# MainSchematic.net
KiCad netlist of a schematic drawn in Altium Designer
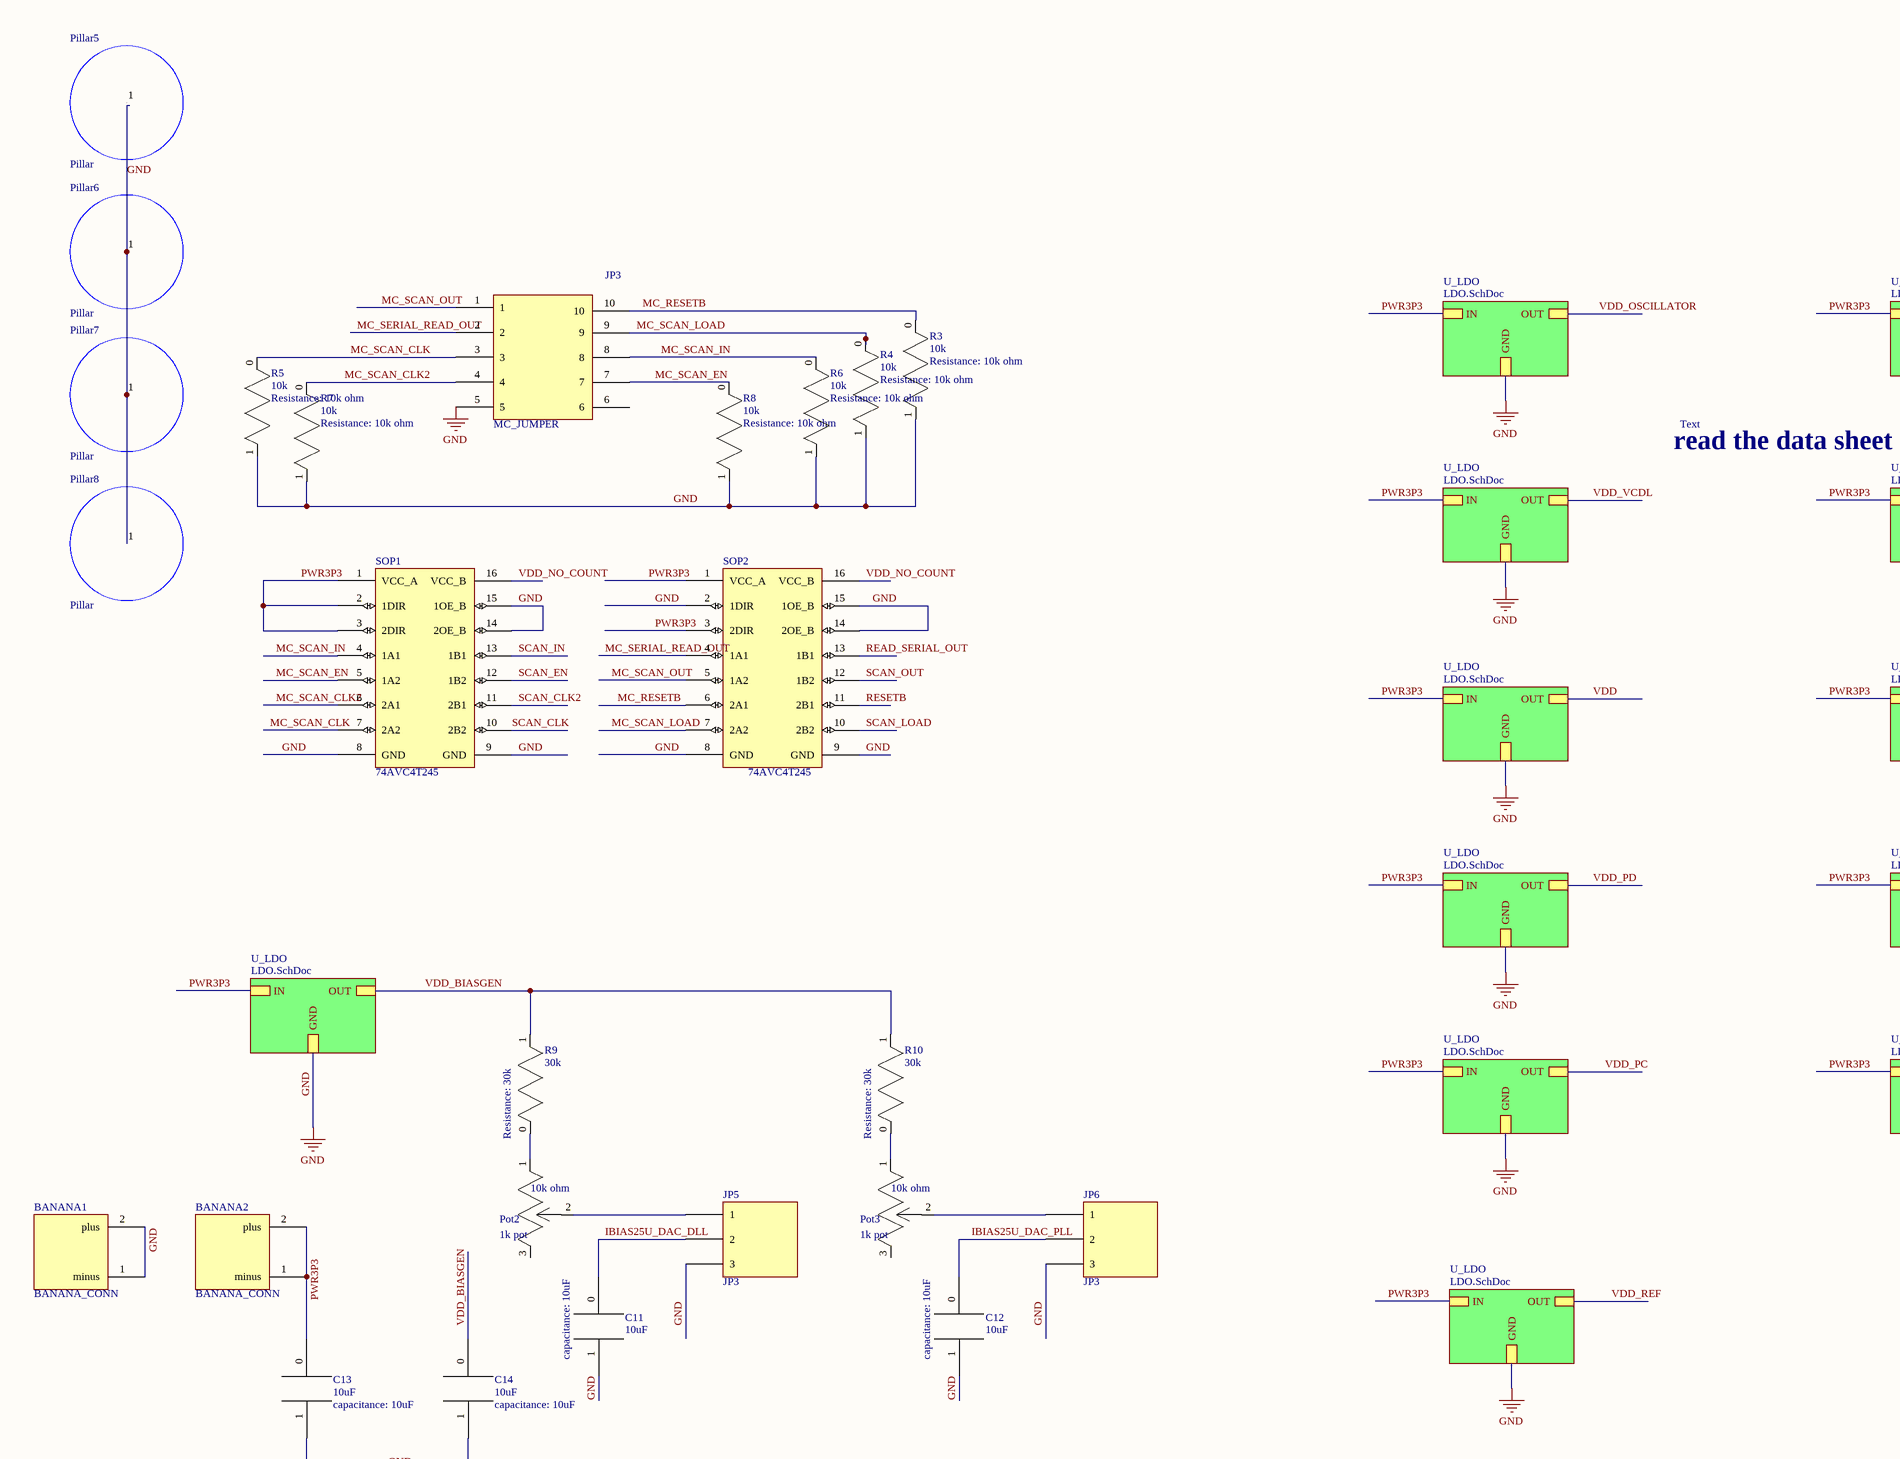
[diagram p0: MainSchematic.SchDoc, top left]
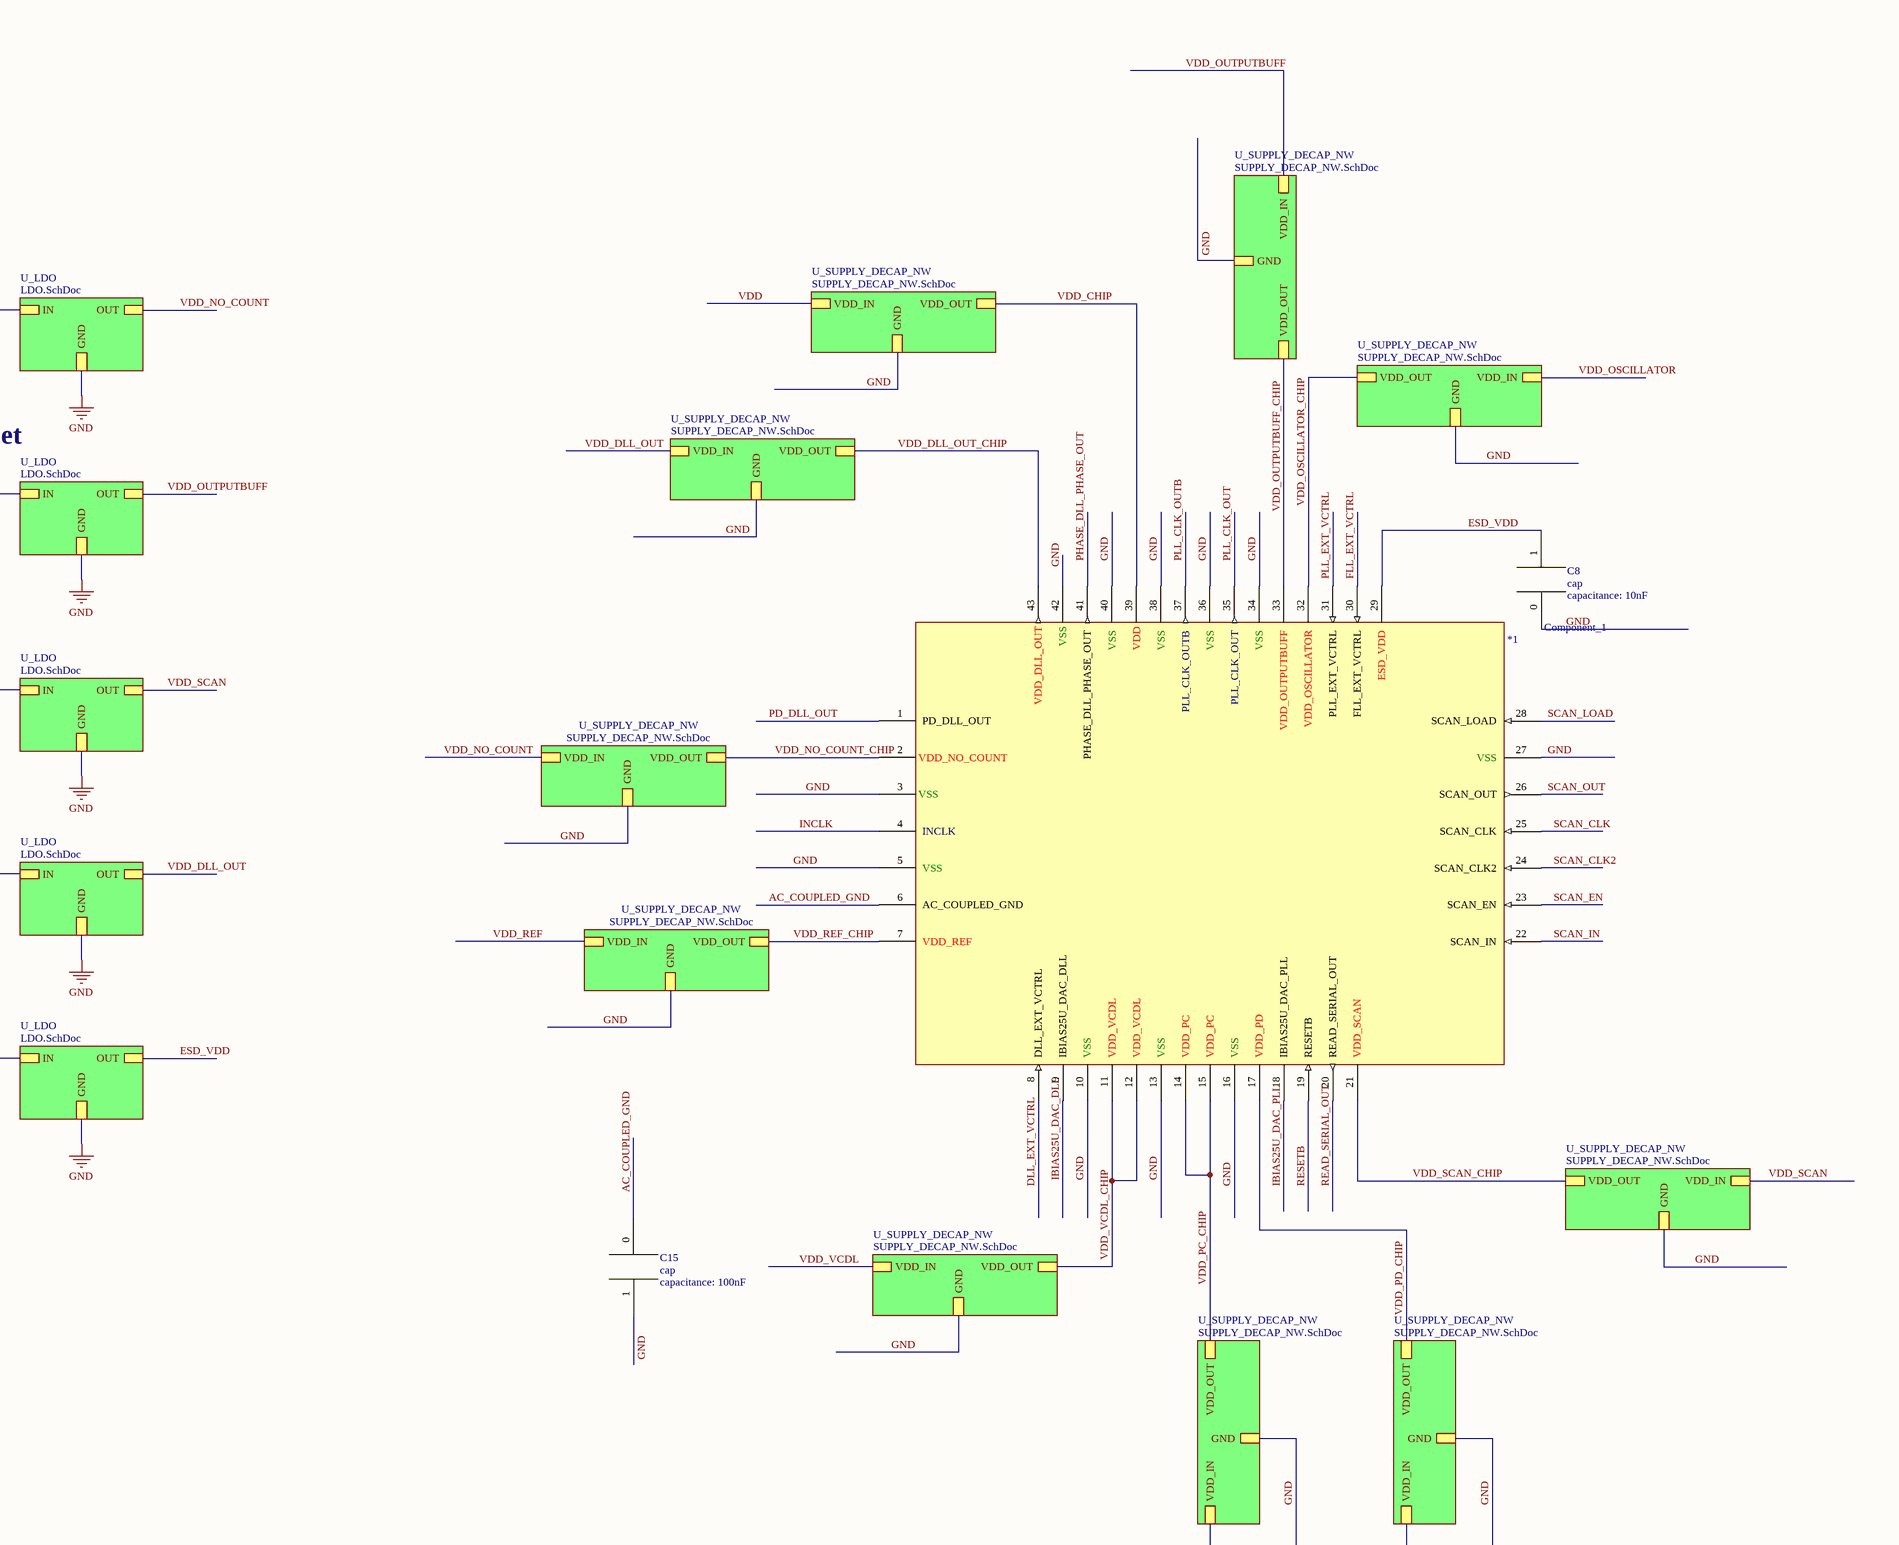
[diagram p1: MainSchematic.SchDoc, top right]
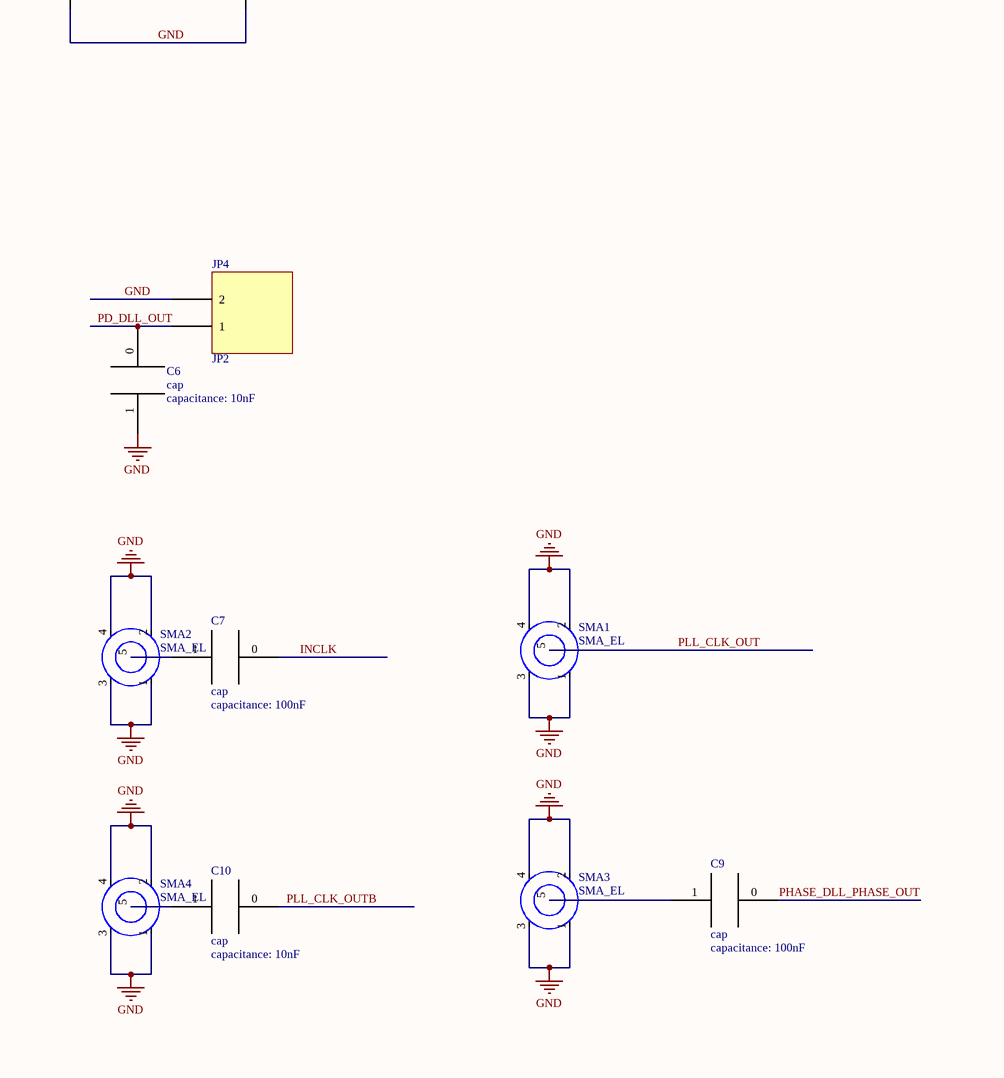
[diagram p2: MainSchematic.SchDoc, bottom left]
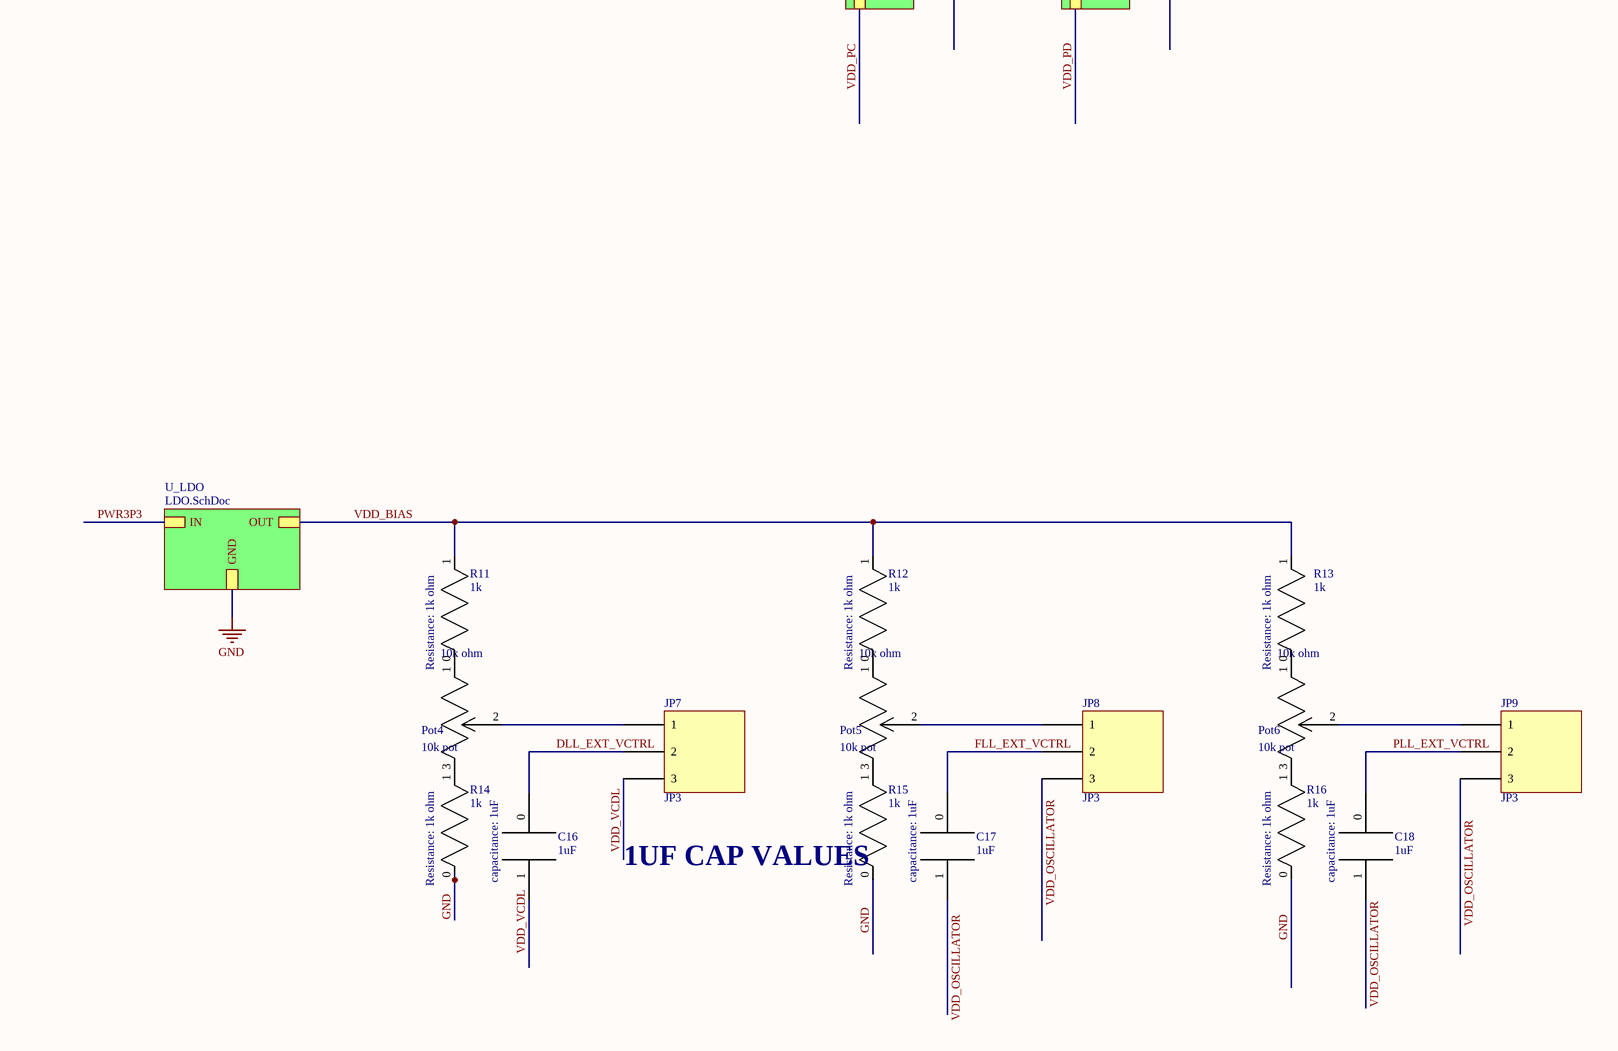
[diagram p3: MainSchematic.SchDoc, bottom right]

(export (version "E")
  (design (tool "Eeschema 10.0.6"))
  (components
    (comp (ref "*1")
      (value "Component_1")
      (footprint "PCBComponent_1")
      (libsource (lib "PLL_CHIP") (part "Component_1"))
    )
    (comp (ref "BANANA1")
      (value "BANANA_CONN")
      (footprint "BANANA_CONN")
      (libsource (lib "Integrated_Library_Da2016") (part "BANANA_CONN"))
    )
    (comp (ref "BANANA2")
      (value "BANANA_CONN")
      (footprint "BANANA_CONN")
      (libsource (lib "Integrated_Library_Da2016") (part "BANANA_CONN"))
    )
    (comp (ref "C6")
      (value "cap")
      (footprint "Capacitor")
      (description "0603cap")
      (fields (field (name "CAPACITANCE") "10nF"))
      (libsource (lib "Integrated_Library_Da2016") (part "cap"))
    )
    (comp (ref "C7")
      (value "cap")
      (footprint "Capacitor")
      (description "0603cap")
      (fields (field (name "CAPACITANCE") "100nF"))
      (libsource (lib "Integrated_Library_Da2016") (part "cap"))
    )
    (comp (ref "C8")
      (value "cap")
      (footprint "Capacitor")
      (description "0603cap")
      (fields (field (name "CAPACITANCE") "10nF"))
      (libsource (lib "Integrated_Library_Da2016") (part "cap"))
    )
    (comp (ref "C9")
      (value "cap")
      (footprint "Capacitor")
      (description "0603cap")
      (fields (field (name "CAPACITANCE") "100nF"))
      (libsource (lib "Integrated_Library_Da2016") (part "cap"))
    )
    (comp (ref "C10")
      (value "cap")
      (footprint "Capacitor")
      (description "0603cap")
      (fields (field (name "CAPACITANCE") "10nF"))
      (libsource (lib "Integrated_Library_Da2016") (part "cap"))
    )
    (comp (ref "C11")
      (value "10uF")
      (footprint "Capacitor")
      (description "0603cap")
      (fields (field (name "CAPACITANCE") "10uF"))
      (libsource (lib "Integrated_Library_Da2016") (part "cap"))
    )
    (comp (ref "C12")
      (value "10uF")
      (footprint "Capacitor")
      (description "0603cap")
      (fields (field (name "CAPACITANCE") "10uF"))
      (libsource (lib "Integrated_Library_Da2016") (part "cap"))
    )
    (comp (ref "C13")
      (value "10uF")
      (footprint "Capacitor")
      (description "0603cap")
      (fields (field (name "CAPACITANCE") "10uF"))
      (libsource (lib "Integrated_Library_Da2016") (part "cap"))
    )
    (comp (ref "C14")
      (value "10uF")
      (footprint "Capacitor")
      (description "0603cap")
      (fields (field (name "CAPACITANCE") "10uF"))
      (libsource (lib "Integrated_Library_Da2016") (part "cap"))
    )
    (comp (ref "C15")
      (value "cap")
      (footprint "Capacitor")
      (description "0603cap")
      (fields (field (name "CAPACITANCE") "100nF"))
      (libsource (lib "Integrated_Library_Da2016") (part "cap"))
    )
    (comp (ref "C16")
      (value "1uF")
      (footprint "Capacitor")
      (description "0603cap")
      (fields (field (name "CAPACITANCE") "1uF"))
      (libsource (lib "Integrated_Library_Da2016") (part "cap"))
    )
    (comp (ref "C17")
      (value "1uF")
      (footprint "Capacitor")
      (description "0603cap")
      (fields (field (name "CAPACITANCE") "1uF"))
      (libsource (lib "Integrated_Library_Da2016") (part "cap"))
    )
    (comp (ref "C18")
      (value "1uF")
      (footprint "Capacitor")
      (description "0603cap")
      (fields (field (name "CAPACITANCE") "1uF"))
      (libsource (lib "Integrated_Library_Da2016") (part "cap"))
    )
    (comp (ref "JP3")
      (value "MC_JUMPER")
      (footprint "JUMPER10")
      (description "Jumper_10p")
      (libsource (lib "Integrated_Library_Da2016") (part "Jumper_10"))
    )
    (comp (ref "JP4")
      (value "JP2")
      (footprint "JUMPER2")
      (description "Jumper_2")
      (libsource (lib "Integrated_Library_Da2016") (part "Jumper_2"))
    )
    (comp (ref "JP5")
      (value "JP3")
      (footprint "JUMPER3")
      (description "Jumper_3p")
      (libsource (lib "Integrated_Library_Da2016") (part "Jumper_3"))
    )
    (comp (ref "JP6")
      (value "JP3")
      (footprint "JUMPER3")
      (description "Jumper_3p")
      (libsource (lib "Integrated_Library_Da2016") (part "Jumper_3"))
    )
    (comp (ref "JP7")
      (value "JP3")
      (footprint "JUMPER3")
      (description "Jumper_3p")
      (libsource (lib "Integrated_Library_Da2016") (part "Jumper_3"))
    )
    (comp (ref "JP8")
      (value "JP3")
      (footprint "JUMPER3")
      (description "Jumper_3p")
      (libsource (lib "Integrated_Library_Da2016") (part "Jumper_3"))
    )
    (comp (ref "JP9")
      (value "JP3")
      (footprint "JUMPER3")
      (description "Jumper_3p")
      (libsource (lib "Integrated_Library_Da2016") (part "Jumper_3"))
    )
    (comp (ref "Pillar5")
      (value "Pillar")
      (footprint "Pillar_hole")
      (libsource (lib "Integrated_Library_Da2016") (part "Pillar_hole"))
    )
    (comp (ref "Pillar6")
      (value "Pillar")
      (footprint "Pillar_hole")
      (libsource (lib "Integrated_Library_Da2016") (part "Pillar_hole"))
    )
    (comp (ref "Pillar7")
      (value "Pillar")
      (footprint "Pillar_hole")
      (libsource (lib "Integrated_Library_Da2016") (part "Pillar_hole"))
    )
    (comp (ref "Pillar8")
      (value "Pillar")
      (footprint "Pillar_hole")
      (libsource (lib "Integrated_Library_Da2016") (part "Pillar_hole"))
    )
    (comp (ref "Pot2")
      (value "1k pot")
      (footprint "Pot")
      (description "Variable Resistor")
      (fields (field (name "RESISTANCE") "10k ohm"))
      (libsource (lib "Integrated_Library_Da2016") (part "Pot"))
    )
    (comp (ref "Pot3")
      (value "1k pot")
      (footprint "Pot")
      (description "Variable Resistor")
      (fields (field (name "RESISTANCE") "10k ohm"))
      (libsource (lib "Integrated_Library_Da2016") (part "Pot"))
    )
    (comp (ref "Pot4")
      (value "10k pot")
      (footprint "Pot")
      (description "Variable Resistor")
      (fields (field (name "RESISTANCE") "10k ohm"))
      (libsource (lib "Integrated_Library_Da2016") (part "Pot"))
    )
    (comp (ref "Pot5")
      (value "10k pot")
      (footprint "Pot")
      (description "Variable Resistor")
      (fields (field (name "RESISTANCE") "10k ohm"))
      (libsource (lib "Integrated_Library_Da2016") (part "Pot"))
    )
    (comp (ref "Pot6")
      (value "10k pot")
      (footprint "Pot")
      (description "Variable Resistor")
      (fields (field (name "RESISTANCE") "10k ohm"))
      (libsource (lib "Integrated_Library_Da2016") (part "Pot"))
    )
    (comp (ref "R3")
      (value "10k")
      (footprint "Resistor")
      (description "0603Res")
      (fields (field (name "RESISTANCE") "10k ohm"))
      (libsource (lib "Integrated_Library_Da2016") (part "res"))
    )
    (comp (ref "R4")
      (value "10k")
      (footprint "Resistor")
      (description "0603Res")
      (fields (field (name "RESISTANCE") "10k ohm"))
      (libsource (lib "Integrated_Library_Da2016") (part "res"))
    )
    (comp (ref "R5")
      (value "10k")
      (footprint "Resistor")
      (description "0603Res")
      (fields (field (name "RESISTANCE") "10k ohm"))
      (libsource (lib "Integrated_Library_Da2016") (part "res"))
    )
    (comp (ref "R6")
      (value "10k")
      (footprint "Resistor")
      (description "0603Res")
      (fields (field (name "RESISTANCE") "10k ohm"))
      (libsource (lib "Integrated_Library_Da2016") (part "res"))
    )
    (comp (ref "R7")
      (value "10k")
      (footprint "Resistor")
      (description "0603Res")
      (fields (field (name "RESISTANCE") "10k ohm"))
      (libsource (lib "Integrated_Library_Da2016") (part "res"))
    )
    (comp (ref "R8")
      (value "10k")
      (footprint "Resistor")
      (description "0603Res")
      (fields (field (name "RESISTANCE") "10k ohm"))
      (libsource (lib "Integrated_Library_Da2016") (part "res"))
    )
    (comp (ref "R9")
      (value "30k")
      (footprint "Resistor")
      (description "0603Res")
      (fields (field (name "RESISTANCE") "30k"))
      (libsource (lib "Integrated_Library_Da2016") (part "res"))
    )
    (comp (ref "R10")
      (value "30k")
      (footprint "Resistor")
      (description "0603Res")
      (fields (field (name "RESISTANCE") "30k"))
      (libsource (lib "Integrated_Library_Da2016") (part "res"))
    )
    (comp (ref "R11")
      (value "1k")
      (footprint "Resistor")
      (description "0603Res")
      (fields (field (name "RESISTANCE") "1k ohm"))
      (libsource (lib "Integrated_Library_Da2016") (part "res"))
    )
    (comp (ref "R12")
      (value "1k")
      (footprint "Resistor")
      (description "0603Res")
      (fields (field (name "RESISTANCE") "1k ohm"))
      (libsource (lib "Integrated_Library_Da2016") (part "res"))
    )
    (comp (ref "R13")
      (value "1k")
      (footprint "Resistor")
      (description "0603Res")
      (fields (field (name "RESISTANCE") "1k ohm"))
      (libsource (lib "Integrated_Library_Da2016") (part "res"))
    )
    (comp (ref "R14")
      (value "1k")
      (footprint "Resistor")
      (description "0603Res")
      (fields (field (name "RESISTANCE") "1k ohm"))
      (libsource (lib "Integrated_Library_Da2016") (part "res"))
    )
    (comp (ref "R15")
      (value "1k")
      (footprint "Resistor")
      (description "0603Res")
      (fields (field (name "RESISTANCE") "1k ohm"))
      (libsource (lib "Integrated_Library_Da2016") (part "res"))
    )
    (comp (ref "R16")
      (value "1k")
      (footprint "Resistor")
      (description "0603Res")
      (fields (field (name "RESISTANCE") "1k ohm"))
      (libsource (lib "Integrated_Library_Da2016") (part "res"))
    )
    (comp (ref "SMA1")
      (value "SMA_EL")
      (footprint "SMA_EL")
      (libsource (lib "Integrated_Library_Da2016") (part "SMA_EL"))
    )
    (comp (ref "SMA2")
      (value "SMA_EL")
      (footprint "SMA_EL")
      (libsource (lib "Integrated_Library_Da2016") (part "SMA_EL"))
    )
    (comp (ref "SMA3")
      (value "SMA_EL")
      (footprint "SMA_EL")
      (libsource (lib "Integrated_Library_Da2016") (part "SMA_EL"))
    )
    (comp (ref "SMA4")
      (value "SMA_EL")
      (footprint "SMA_EL")
      (libsource (lib "Integrated_Library_Da2016") (part "SMA_EL"))
    )
    (comp (ref "SOP1")
      (value "74AVC4T245")
      (footprint "74AVC4T245")
      (description "74AVC4T245 Voltage Shifter")
      (libsource (lib "Integrated_Library_Da2016") (part "74AVC4T245"))
    )
    (comp (ref "SOP2")
      (value "74AVC4T245")
      (footprint "74AVC4T245")
      (description "74AVC4T245 Voltage Shifter")
      (libsource (lib "Integrated_Library_Da2016") (part "74AVC4T245"))
    )
  )
  (nets
    (net (code "1") (name "/AC_COUPLED_GND") (class "Default")
      (node (ref "*1") (pin "6") (pinfunction "AC_COUPLED_GND_6") (pintype "power_in"))
      (node (ref "C15") (pin "0") (pinfunction "0_0") (pintype "passive"))
    )
    (net (code "2") (name "/DLL_EXT_VCTRL") (class "Default")
      (node (ref "*1") (pin "8") (pinfunction "DLL_EXT_VCTRL_8") (pintype "input"))
      (node (ref "C16") (pin "0") (pinfunction "0_0") (pintype "passive"))
      (node (ref "JP7") (pin "2") (pinfunction "2_2") (pintype "passive"))
    )
    (net (code "3") (name "/ESD_VDD") (class "Default")
      (node (ref "*1") (pin "29") (pinfunction "ESD_VDD_29") (pintype "power_in"))
      (node (ref "C8") (pin "1") (pinfunction "1_1") (pintype "passive"))
    )
    (net (code "4") (name "/FLL_EXT_VCTRL") (class "Default")
      (node (ref "*1") (pin "30") (pinfunction "FLL_EXT_VCTRL_30") (pintype "input"))
      (node (ref "C17") (pin "0") (pinfunction "0_0") (pintype "passive"))
      (node (ref "JP8") (pin "2") (pinfunction "2_2") (pintype "passive"))
    )
    (net (code "5") (name "/IBIAS25U_DAC_DLL") (class "Default")
      (node (ref "*1") (pin "9") (pinfunction "IBIAS25U_DAC_DLL_9") (pintype "passive"))
      (node (ref "C11") (pin "0") (pinfunction "0_0") (pintype "passive"))
      (node (ref "JP5") (pin "2") (pinfunction "2_2") (pintype "passive"))
    )
    (net (code "6") (name "/IBIAS25U_DAC_PLL") (class "Default")
      (node (ref "*1") (pin "18") (pinfunction "IBIAS25U_DAC_PLL_18") (pintype "passive"))
      (node (ref "C12") (pin "0") (pinfunction "0_0") (pintype "passive"))
      (node (ref "JP6") (pin "2") (pinfunction "2_2") (pintype "passive"))
    )
    (net (code "7") (name "/INCLK") (class "Default")
      (node (ref "*1") (pin "4") (pinfunction "INCLK_4") (pintype "passive"))
      (node (ref "C7") (pin "0") (pinfunction "0_0") (pintype "passive"))
    )
    (net (code "8") (name "/MC_RESETB") (class "Default")
      (node (ref "JP3") (pin "10") (pinfunction "10_10") (pintype "passive"))
      (node (ref "R3") (pin "0") (pinfunction "0_0") (pintype "passive"))
      (node (ref "SOP2") (pin "6") (pinfunction "2A1_6") (pintype "bidirectional"))
    )
    (net (code "9") (name "/MC_SCAN_CLK") (class "Default")
      (node (ref "JP3") (pin "3") (pinfunction "3_3") (pintype "passive"))
      (node (ref "R5") (pin "0") (pinfunction "0_0") (pintype "passive"))
      (node (ref "SOP1") (pin "7") (pinfunction "2A2_7") (pintype "bidirectional"))
    )
    (net (code "10") (name "/MC_SCAN_CLK2") (class "Default")
      (node (ref "JP3") (pin "4") (pinfunction "4_4") (pintype "passive"))
      (node (ref "R7") (pin "0") (pinfunction "0_0") (pintype "passive"))
      (node (ref "SOP1") (pin "6") (pinfunction "2A1_6") (pintype "bidirectional"))
    )
    (net (code "11") (name "/MC_SCAN_EN") (class "Default")
      (node (ref "JP3") (pin "7") (pinfunction "7_7") (pintype "passive"))
      (node (ref "R8") (pin "0") (pinfunction "0_0") (pintype "passive"))
      (node (ref "SOP1") (pin "5") (pinfunction "1A2_5") (pintype "bidirectional"))
    )
    (net (code "12") (name "/MC_SCAN_IN") (class "Default")
      (node (ref "JP3") (pin "8") (pinfunction "8_8") (pintype "passive"))
      (node (ref "R6") (pin "0") (pinfunction "0_0") (pintype "passive"))
      (node (ref "SOP1") (pin "4") (pinfunction "1A1_4") (pintype "bidirectional"))
    )
    (net (code "13") (name "/MC_SCAN_LOAD") (class "Default")
      (node (ref "JP3") (pin "9") (pinfunction "9_9") (pintype "passive"))
      (node (ref "R4") (pin "0") (pinfunction "0_0") (pintype "passive"))
      (node (ref "SOP2") (pin "7") (pinfunction "2A2_7") (pintype "bidirectional"))
    )
    (net (code "14") (name "/MC_SCAN_OUT") (class "Default")
      (node (ref "JP3") (pin "1") (pinfunction "1_1") (pintype "passive"))
      (node (ref "SOP2") (pin "5") (pinfunction "1A2_5") (pintype "bidirectional"))
    )
    (net (code "15") (name "/MC_SERIAL_READ_OUT") (class "Default")
      (node (ref "JP3") (pin "2") (pinfunction "2_2") (pintype "passive"))
      (node (ref "SOP2") (pin "4") (pinfunction "1A1_4") (pintype "bidirectional"))
    )
    (net (code "16") (name "/PD_DLL_OUT") (class "Default")
      (node (ref "*1") (pin "1") (pinfunction "PD_DLL_OUT_1") (pintype "passive"))
      (node (ref "C6") (pin "0") (pinfunction "0_0") (pintype "passive"))
      (node (ref "JP4") (pin "1") (pinfunction "1_1") (pintype "passive"))
    )
    (net (code "17") (name "/PHASE_DLL_PHASE_OUT") (class "Default")
      (node (ref "*1") (pin "41") (pinfunction "PHASE_DLL_PHASE_OUT_41") (pintype "output"))
      (node (ref "C9") (pin "0") (pinfunction "0_0") (pintype "passive"))
    )
    (net (code "18") (name "/PLL_CLK_OUT") (class "Default")
      (node (ref "*1") (pin "35") (pinfunction "PLL_CLK_OUT_35") (pintype "output"))
      (node (ref "SMA1") (pin "5") (pinfunction "5_5") (pintype "passive"))
    )
    (net (code "19") (name "/PLL_CLK_OUTB") (class "Default")
      (node (ref "*1") (pin "37") (pinfunction "PLL_CLK_OUTB_37") (pintype "output"))
      (node (ref "C10") (pin "0") (pinfunction "0_0") (pintype "passive"))
    )
    (net (code "20") (name "/PLL_EXT_VCTRL") (class "Default")
      (node (ref "*1") (pin "31") (pinfunction "PLL_EXT_VCTRL_31") (pintype "input"))
      (node (ref "C18") (pin "0") (pinfunction "0_0") (pintype "passive"))
      (node (ref "JP9") (pin "2") (pinfunction "2_2") (pintype "passive"))
    )
    (net (code "21") (name "/PWR3P3") (class "Default")
      (node (ref "BANANA2") (pin "1") (pinfunction "minus_1") (pintype "passive"))
      (node (ref "BANANA2") (pin "2") (pinfunction "plus_2") (pintype "passive"))
      (node (ref "C13") (pin "0") (pinfunction "0_0") (pintype "passive"))
      (node (ref "SOP1") (pin "1") (pinfunction "VCC_A_1") (pintype "power_in"))
      (node (ref "SOP1") (pin "2") (pinfunction "1DIR_2") (pintype "bidirectional"))
      (node (ref "SOP1") (pin "3") (pinfunction "2DIR_3") (pintype "bidirectional"))
      (node (ref "SOP2") (pin "1") (pinfunction "VCC_A_1") (pintype "power_in"))
      (node (ref "SOP2") (pin "3") (pinfunction "2DIR_3") (pintype "bidirectional"))
    )
    (net (code "22") (name "/READ_SERIAL_OUT") (class "Default")
      (node (ref "*1") (pin "20") (pinfunction "READ_SERIAL_OUT_20") (pintype "output"))
      (node (ref "SOP2") (pin "13") (pinfunction "1B1_13") (pintype "bidirectional"))
    )
    (net (code "23") (name "/RESETB") (class "Default")
      (node (ref "*1") (pin "19") (pinfunction "RESETB_19") (pintype "input"))
      (node (ref "SOP2") (pin "11") (pinfunction "2B1_11") (pintype "bidirectional"))
    )
    (net (code "24") (name "/SCAN_CLK") (class "Default")
      (node (ref "*1") (pin "25") (pinfunction "SCAN_CLK_25") (pintype "input"))
      (node (ref "SOP1") (pin "10") (pinfunction "2B2_10") (pintype "bidirectional"))
    )
    (net (code "25") (name "/SCAN_CLK2") (class "Default")
      (node (ref "*1") (pin "24") (pinfunction "SCAN_CLK2_24") (pintype "input"))
      (node (ref "SOP1") (pin "11") (pinfunction "2B1_11") (pintype "bidirectional"))
    )
    (net (code "26") (name "/SCAN_EN") (class "Default")
      (node (ref "*1") (pin "23") (pinfunction "SCAN_EN_23") (pintype "input"))
      (node (ref "SOP1") (pin "12") (pinfunction "1B2_12") (pintype "bidirectional"))
    )
    (net (code "27") (name "/SCAN_IN") (class "Default")
      (node (ref "*1") (pin "22") (pinfunction "SCAN_IN_22") (pintype "input"))
      (node (ref "SOP1") (pin "13") (pinfunction "1B1_13") (pintype "bidirectional"))
    )
    (net (code "28") (name "/SCAN_LOAD") (class "Default")
      (node (ref "*1") (pin "28") (pinfunction "SCAN_LOAD_28") (pintype "input"))
      (node (ref "SOP2") (pin "10") (pinfunction "2B2_10") (pintype "bidirectional"))
    )
    (net (code "29") (name "/SCAN_OUT") (class "Default")
      (node (ref "*1") (pin "26") (pinfunction "SCAN_OUT_26") (pintype "output"))
      (node (ref "SOP2") (pin "12") (pinfunction "1B2_12") (pintype "bidirectional"))
    )
    (net (code "31") (name "/VDD_BIAS") (class "Default")
      (node (ref "R11") (pin "1") (pinfunction "1_1") (pintype "passive"))
      (node (ref "R12") (pin "1") (pinfunction "1_1") (pintype "passive"))
      (node (ref "R13") (pin "1") (pinfunction "1_1") (pintype "passive"))
    )
    (net (code "32") (name "/VDD_BIASGEN") (class "Default")
      (node (ref "C14") (pin "0") (pinfunction "0_0") (pintype "passive"))
      (node (ref "R10") (pin "1") (pinfunction "1_1") (pintype "passive"))
      (node (ref "R9") (pin "1") (pinfunction "1_1") (pintype "passive"))
    )
    (net (code "33") (name "/VDD_CHIP") (class "Default")
      (node (ref "*1") (pin "39") (pinfunction "VDD_39") (pintype "power_in"))
    )
    (net (code "35") (name "/VDD_DLL_OUT_CHIP") (class "Default")
      (node (ref "*1") (pin "43") (pinfunction "VDD_DLL_OUT_43") (pintype "output"))
    )
    (net (code "36") (name "/VDD_NO_COUNT") (class "Default")
      (node (ref "SOP1") (pin "16") (pinfunction "VCC_B_16") (pintype "power_in"))
      (node (ref "SOP2") (pin "16") (pinfunction "VCC_B_16") (pintype "power_in"))
    )
    (net (code "37") (name "/VDD_NO_COUNT_CHIP") (class "Default")
      (node (ref "*1") (pin "2") (pinfunction "VDD_NO_COUNT_2") (pintype "passive"))
    )
    (net (code "38") (name "/VDD_OSCILLATOR") (class "Default")
      (node (ref "C17") (pin "1") (pinfunction "1_1") (pintype "passive"))
      (node (ref "C18") (pin "1") (pinfunction "1_1") (pintype "passive"))
      (node (ref "JP8") (pin "3") (pinfunction "3_3") (pintype "passive"))
      (node (ref "JP9") (pin "3") (pinfunction "3_3") (pintype "passive"))
    )
    (net (code "39") (name "/VDD_OSCILLATOR_CHIP") (class "Default")
      (node (ref "*1") (pin "32") (pinfunction "VDD_OSCILLATOR_32") (pintype "power_in"))
    )
    (net (code "41") (name "/VDD_OUTPUTBUFF_CHIP") (class "Default")
      (node (ref "*1") (pin "33") (pinfunction "VDD_OUTPUTBUFF_33") (pintype "power_in"))
    )
    (net (code "43") (name "/VDD_PC_CHIP") (class "Default")
      (node (ref "*1") (pin "14") (pinfunction "VDD_PC_14") (pintype "power_in"))
      (node (ref "*1") (pin "15") (pinfunction "VDD_PC_15") (pintype "power_in"))
    )
    (net (code "45") (name "/VDD_PD_CHIP") (class "Default")
      (node (ref "*1") (pin "17") (pinfunction "VDD_PD_17") (pintype "power_in"))
    )
    (net (code "47") (name "/VDD_REF_CHIP") (class "Default")
      (node (ref "*1") (pin "7") (pinfunction "VDD_REF_7") (pintype "power_in"))
    )
    (net (code "49") (name "/VDD_SCAN_CHIP") (class "Default")
      (node (ref "*1") (pin "21") (pinfunction "VDD_SCAN_21") (pintype "power_in"))
    )
    (net (code "50") (name "/VDD_VCDL") (class "Default")
      (node (ref "C16") (pin "1") (pinfunction "1_1") (pintype "passive"))
      (node (ref "JP7") (pin "3") (pinfunction "3_3") (pintype "passive"))
    )
    (net (code "51") (name "/VDD_VCDL_CHIP") (class "Default")
      (node (ref "*1") (pin "11") (pinfunction "VDD_VCDL_11") (pintype "power_in"))
      (node (ref "*1") (pin "12") (pinfunction "VDD_VCDL_12") (pintype "power_in"))
    )
    (net (code "52") (name "GND") (class "Default")
      (node (ref "*1") (pin "10") (pinfunction "VSS_10") (pintype "power_in"))
      (node (ref "*1") (pin "13") (pinfunction "VSS_13") (pintype "power_in"))
      (node (ref "*1") (pin "16") (pinfunction "VSS_16") (pintype "power_in"))
      (node (ref "*1") (pin "27") (pinfunction "VSS_27") (pintype "power_in"))
      (node (ref "*1") (pin "3") (pinfunction "VSS_3") (pintype "power_in"))
      (node (ref "*1") (pin "34") (pinfunction "VSS_34") (pintype "power_in"))
      (node (ref "*1") (pin "36") (pinfunction "VSS_36") (pintype "power_in"))
      (node (ref "*1") (pin "38") (pinfunction "VSS_38") (pintype "power_in"))
      (node (ref "*1") (pin "40") (pinfunction "VSS_40") (pintype "power_in"))
      (node (ref "*1") (pin "42") (pinfunction "VSS_42") (pintype "power_in"))
      (node (ref "*1") (pin "5") (pinfunction "VSS_5") (pintype "power_in"))
      (node (ref "BANANA1") (pin "1") (pinfunction "minus_1") (pintype "passive"))
      (node (ref "BANANA1") (pin "2") (pinfunction "plus_2") (pintype "passive"))
      (node (ref "C11") (pin "1") (pinfunction "1_1") (pintype "passive"))
      (node (ref "C12") (pin "1") (pinfunction "1_1") (pintype "passive"))
      (node (ref "C13") (pin "1") (pinfunction "1_1") (pintype "passive"))
      (node (ref "C14") (pin "1") (pinfunction "1_1") (pintype "passive"))
      (node (ref "C15") (pin "1") (pinfunction "1_1") (pintype "passive"))
      (node (ref "C6") (pin "1") (pinfunction "1_1") (pintype "passive"))
      (node (ref "C8") (pin "0") (pinfunction "0_0") (pintype "passive"))
      (node (ref "JP3") (pin "5") (pinfunction "5_5") (pintype "passive"))
      (node (ref "JP4") (pin "2") (pinfunction "2_2") (pintype "passive"))
      (node (ref "JP5") (pin "3") (pinfunction "3_3") (pintype "passive"))
      (node (ref "JP6") (pin "3") (pinfunction "3_3") (pintype "passive"))
      (node (ref "Pillar6") (pin "1") (pinfunction "1_1") (pintype "passive"))
      (node (ref "Pillar7") (pin "1") (pinfunction "1_1") (pintype "passive"))
      (node (ref "Pillar8") (pin "1") (pinfunction "1_1") (pintype "passive"))
      (node (ref "R14") (pin "0") (pinfunction "0_0") (pintype "passive"))
      (node (ref "R15") (pin "0") (pinfunction "0_0") (pintype "passive"))
      (node (ref "R16") (pin "0") (pinfunction "0_0") (pintype "passive"))
      (node (ref "R3") (pin "1") (pinfunction "1_1") (pintype "passive"))
      (node (ref "R4") (pin "1") (pinfunction "1_1") (pintype "passive"))
      (node (ref "R5") (pin "1") (pinfunction "1_1") (pintype "passive"))
      (node (ref "R6") (pin "1") (pinfunction "1_1") (pintype "passive"))
      (node (ref "R7") (pin "1") (pinfunction "1_1") (pintype "passive"))
      (node (ref "R8") (pin "1") (pinfunction "1_1") (pintype "passive"))
      (node (ref "SMA1") (pin "1") (pinfunction "1_1") (pintype "passive"))
      (node (ref "SMA1") (pin "2") (pinfunction "2_2") (pintype "passive"))
      (node (ref "SMA1") (pin "3") (pinfunction "3_3") (pintype "passive"))
      (node (ref "SMA1") (pin "4") (pinfunction "4_4") (pintype "passive"))
      (node (ref "SMA2") (pin "1") (pinfunction "1_1") (pintype "passive"))
      (node (ref "SMA2") (pin "2") (pinfunction "2_2") (pintype "passive"))
      (node (ref "SMA2") (pin "3") (pinfunction "3_3") (pintype "passive"))
      (node (ref "SMA2") (pin "4") (pinfunction "4_4") (pintype "passive"))
      (node (ref "SMA3") (pin "1") (pinfunction "1_1") (pintype "passive"))
      (node (ref "SMA3") (pin "2") (pinfunction "2_2") (pintype "passive"))
      (node (ref "SMA3") (pin "3") (pinfunction "3_3") (pintype "passive"))
      (node (ref "SMA3") (pin "4") (pinfunction "4_4") (pintype "passive"))
      (node (ref "SMA4") (pin "1") (pinfunction "1_1") (pintype "passive"))
      (node (ref "SMA4") (pin "2") (pinfunction "2_2") (pintype "passive"))
      (node (ref "SMA4") (pin "3") (pinfunction "3_3") (pintype "passive"))
      (node (ref "SMA4") (pin "4") (pinfunction "4_4") (pintype "passive"))
      (node (ref "SOP1") (pin "14") (pinfunction "2OE_B_14") (pintype "bidirectional"))
      (node (ref "SOP1") (pin "15") (pinfunction "1OE_B_15") (pintype "bidirectional"))
      (node (ref "SOP1") (pin "8") (pinfunction "GND_8") (pintype "power_in"))
      (node (ref "SOP1") (pin "9") (pinfunction "GND_9") (pintype "power_in"))
      (node (ref "SOP2") (pin "14") (pinfunction "2OE_B_14") (pintype "bidirectional"))
      (node (ref "SOP2") (pin "15") (pinfunction "1OE_B_15") (pintype "bidirectional"))
      (node (ref "SOP2") (pin "2") (pinfunction "1DIR_2") (pintype "bidirectional"))
      (node (ref "SOP2") (pin "8") (pinfunction "GND_8") (pintype "power_in"))
      (node (ref "SOP2") (pin "9") (pinfunction "GND_9") (pintype "power_in"))
    )
    (net (code "53") (name "Net-(C7-Pad1)") (class "Default")
      (node (ref "C7") (pin "1") (pinfunction "1_1") (pintype "passive"))
      (node (ref "SMA2") (pin "5") (pinfunction "5_5") (pintype "passive"))
    )
    (net (code "54") (name "Net-(C9-Pad1)") (class "Default")
      (node (ref "C9") (pin "1") (pinfunction "1_1") (pintype "passive"))
      (node (ref "SMA3") (pin "5") (pinfunction "5_5") (pintype "passive"))
    )
    (net (code "55") (name "Net-(C10-Pad1)") (class "Default")
      (node (ref "C10") (pin "1") (pinfunction "1_1") (pintype "passive"))
      (node (ref "SMA4") (pin "5") (pinfunction "5_5") (pintype "passive"))
    )
    (net (code "56") (name "Net-(JP5-Pad1)") (class "Default")
      (node (ref "JP5") (pin "1") (pinfunction "1_1") (pintype "passive"))
      (node (ref "Pot2") (pin "2") (pinfunction "2_2") (pintype "passive"))
    )
    (net (code "57") (name "Net-(JP6-Pad1)") (class "Default")
      (node (ref "JP6") (pin "1") (pinfunction "1_1") (pintype "passive"))
      (node (ref "Pot3") (pin "2") (pinfunction "2_2") (pintype "passive"))
    )
    (net (code "58") (name "Net-(JP7-Pad1)") (class "Default")
      (node (ref "JP7") (pin "1") (pinfunction "1_1") (pintype "passive"))
      (node (ref "Pot4") (pin "2") (pinfunction "2_2") (pintype "passive"))
    )
    (net (code "59") (name "Net-(JP8-Pad1)") (class "Default")
      (node (ref "JP8") (pin "1") (pinfunction "1_1") (pintype "passive"))
      (node (ref "Pot5") (pin "2") (pinfunction "2_2") (pintype "passive"))
    )
    (net (code "60") (name "Net-(JP9-Pad1)") (class "Default")
      (node (ref "JP9") (pin "1") (pinfunction "1_1") (pintype "passive"))
      (node (ref "Pot6") (pin "2") (pinfunction "2_2") (pintype "passive"))
    )
    (net (code "61") (name "Net-(Pot2-Pad1)") (class "Default")
      (node (ref "Pot2") (pin "1") (pinfunction "1_1") (pintype "passive"))
      (node (ref "R9") (pin "0") (pinfunction "0_0") (pintype "passive"))
    )
    (net (code "62") (name "Net-(Pot3-Pad1)") (class "Default")
      (node (ref "Pot3") (pin "1") (pinfunction "1_1") (pintype "passive"))
      (node (ref "R10") (pin "0") (pinfunction "0_0") (pintype "passive"))
    )
    (net (code "63") (name "Net-(Pot4-Pad1)") (class "Default")
      (node (ref "Pot4") (pin "1") (pinfunction "1_1") (pintype "passive"))
      (node (ref "R11") (pin "0") (pinfunction "0_0") (pintype "passive"))
    )
    (net (code "64") (name "Net-(Pot4-Pad3)") (class "Default")
      (node (ref "Pot4") (pin "3") (pinfunction "3_3") (pintype "passive"))
      (node (ref "R14") (pin "1") (pinfunction "1_1") (pintype "passive"))
    )
    (net (code "65") (name "Net-(Pot5-Pad1)") (class "Default")
      (node (ref "Pot5") (pin "1") (pinfunction "1_1") (pintype "passive"))
      (node (ref "R12") (pin "0") (pinfunction "0_0") (pintype "passive"))
    )
    (net (code "66") (name "Net-(Pot5-Pad3)") (class "Default")
      (node (ref "Pot5") (pin "3") (pinfunction "3_3") (pintype "passive"))
      (node (ref "R15") (pin "1") (pinfunction "1_1") (pintype "passive"))
    )
    (net (code "67") (name "Net-(Pot6-Pad1)") (class "Default")
      (node (ref "Pot6") (pin "1") (pinfunction "1_1") (pintype "passive"))
      (node (ref "R13") (pin "0") (pinfunction "0_0") (pintype "passive"))
    )
    (net (code "68") (name "Net-(Pot6-Pad3)") (class "Default")
      (node (ref "Pot6") (pin "3") (pinfunction "3_3") (pintype "passive"))
      (node (ref "R16") (pin "1") (pinfunction "1_1") (pintype "passive"))
    )
    (net (code "69") (name "unconnected-(JP3-Pad6)") (class "Default")
      (node (ref "JP3") (pin "6") (pinfunction "6_6") (pintype "passive"))
    )
    (net (code "70") (name "unconnected-(Pillar5-Pad1)") (class "Default")
      (node (ref "Pillar5") (pin "1") (pinfunction "1_1") (pintype "passive"))
    )
    (net (code "71") (name "unconnected-(Pot2-Pad3)") (class "Default")
      (node (ref "Pot2") (pin "3") (pinfunction "3_3") (pintype "passive"))
    )
    (net (code "72") (name "unconnected-(Pot3-Pad3)") (class "Default")
      (node (ref "Pot3") (pin "3") (pinfunction "3_3") (pintype "passive"))
    )
  )
)
